# EasyEDA_SCH_5_5-OLED-to-RP5-MIPI.net
KiCad netlist of a schematic drawn in EasyEDA
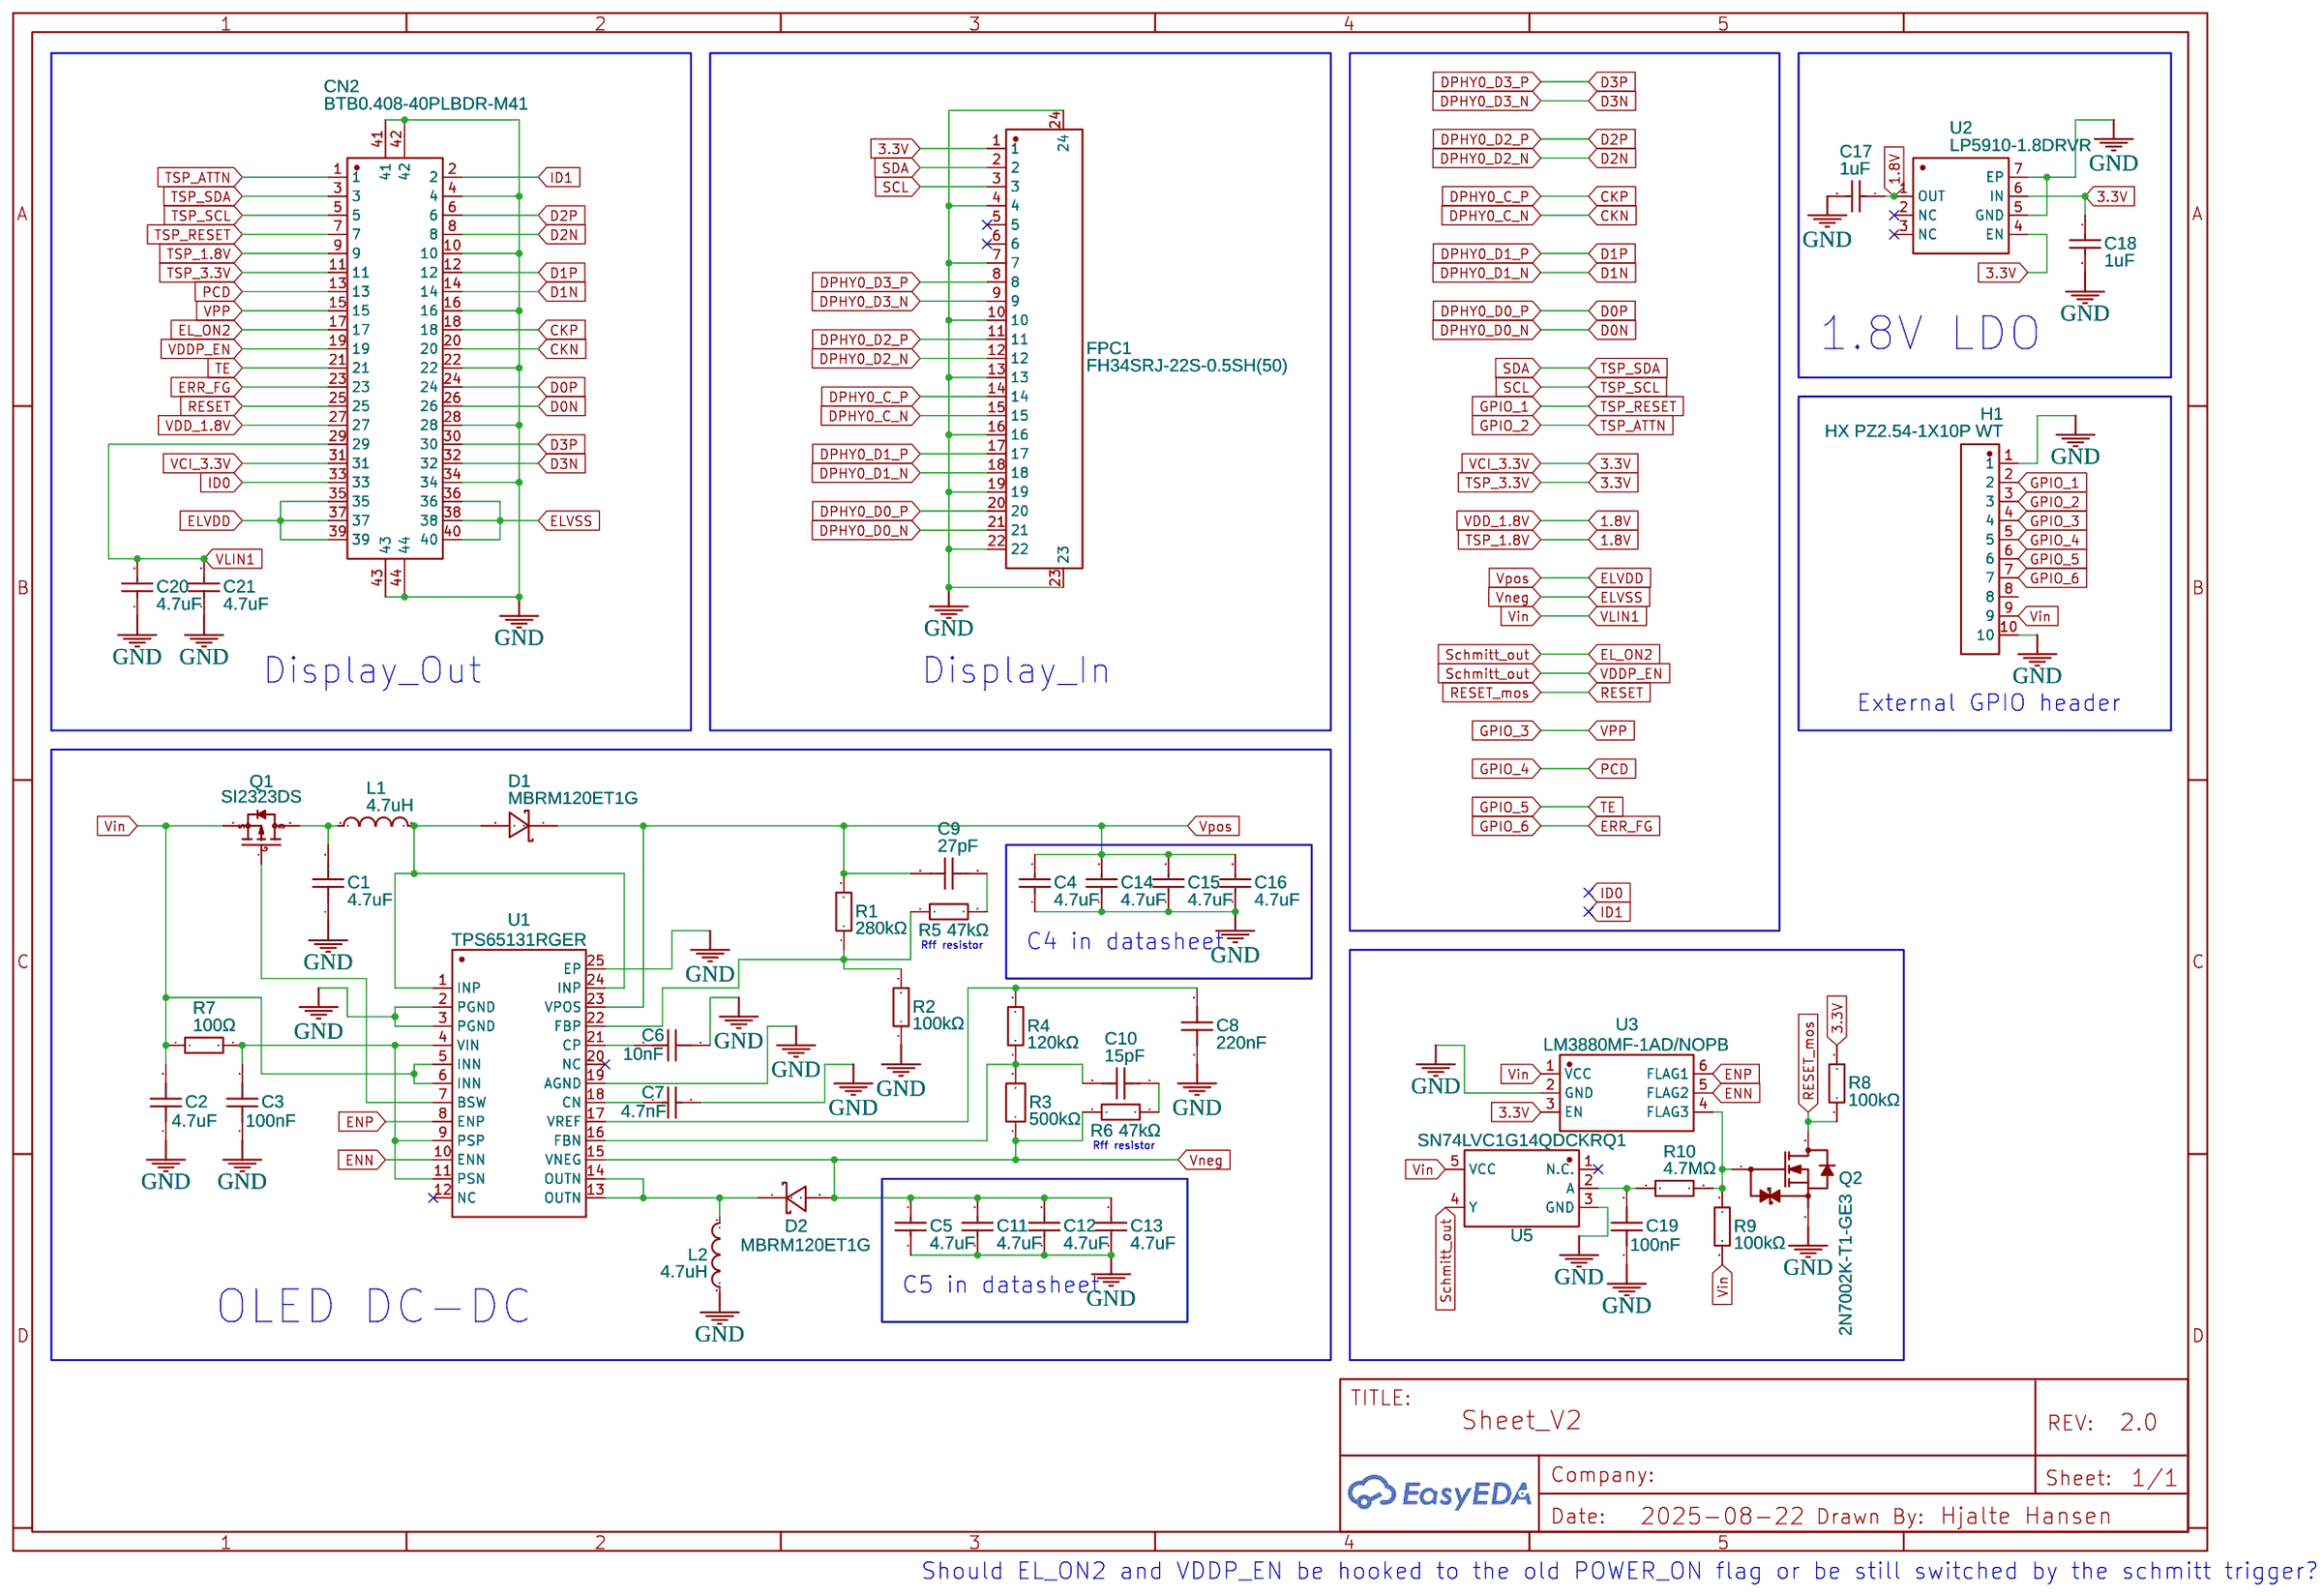
[diagram p0: schematic sheet]

(export (version "E")
  (design (tool "Eeschema 10.0.6"))
  (components
    (comp (ref "C1")
      (value "4.7uF")
      (fields
        (field (name "Manufacturer Part") "CL05A475MQ5NRNC")
        (field (name "Manufacturer") "SAMSUNG(三星)")
      )
      (libsource (lib "") (part "CL05A475MQ5NRNC_C307423"))
    )
    (comp (ref "C2")
      (value "4.7uF")
      (fields
        (field (name "Manufacturer Part") "CL05A475MQ5NRNC")
        (field (name "Manufacturer") "SAMSUNG(三星)")
      )
      (libsource (lib "") (part "CL05A475MQ5NRNC_C307423"))
    )
    (comp (ref "C3")
      (value "100nF")
      (fields
        (field (name "Manufacturer Part") "CL05B104KP5NNNC")
        (field (name "Manufacturer") "SAMSUNG(三星)")
      )
      (libsource (lib "") (part "CL05B104KP5NNNC"))
    )
    (comp (ref "C4")
      (value "4.7uF")
      (fields
        (field (name "Manufacturer Part") "CL21A475KAQNNNE")
        (field (name "Manufacturer") "SAMSUNG(三星)")
      )
      (libsource (lib "") (part "CL21A475KAQNNNE"))
    )
    (comp (ref "C5")
      (value "4.7uF")
      (fields
        (field (name "Manufacturer Part") "CL21A475KAQNNNE")
        (field (name "Manufacturer") "SAMSUNG(三星)")
      )
      (libsource (lib "") (part "CL21A475KAQNNNE"))
    )
    (comp (ref "C6")
      (value "10nF")
      (fields
        (field (name "Manufacturer Part") "CL05B103KO5NNNC")
        (field (name "Manufacturer") "SAMSUNG(三星)")
      )
      (libsource (lib "") (part "CL05B103KO5NNNC"))
    )
    (comp (ref "C7")
      (value "4.7nF")
      (fields
        (field (name "Manufacturer Part") "CL10B472KB8NNNC")
        (field (name "Manufacturer") "SAMSUNG(三星)")
      )
      (libsource (lib "") (part "CL10B472KB8NNNC"))
    )
    (comp (ref "C8")
      (value "220nF")
      (fields
        (field (name "Manufacturer Part") "CL05A224KQ5NNNC")
        (field (name "Manufacturer") "SAMSUNG(三星)")
      )
      (libsource (lib "") (part "CL05A224KQ5NNNC"))
    )
    (comp (ref "C9")
      (value "27pF")
      (fields
        (field (name "Manufacturer Part") "CC0603JRNPO7BN270")
        (field (name "Manufacturer") "YAGEO(国巨)")
      )
      (libsource (lib "") (part "CC0603JRNPO7BN270"))
    )
    (comp (ref "C10")
      (value "15pF")
      (fields
        (field (name "Manufacturer Part") "CC0402KRNPO7BN150")
        (field (name "Manufacturer") "YAGEO(国巨)")
      )
      (libsource (lib "") (part "CC0402KRNPO7BN150"))
    )
    (comp (ref "C11")
      (value "4.7uF")
      (fields
        (field (name "Manufacturer Part") "CL21A475KAQNNNE")
        (field (name "Manufacturer") "SAMSUNG(三星)")
      )
      (libsource (lib "") (part "CL21A475KAQNNNE"))
    )
    (comp (ref "C12")
      (value "4.7uF")
      (fields
        (field (name "Manufacturer Part") "CL21A475KAQNNNE")
        (field (name "Manufacturer") "SAMSUNG(三星)")
      )
      (libsource (lib "") (part "CL21A475KAQNNNE"))
    )
    (comp (ref "C13")
      (value "4.7uF")
      (fields
        (field (name "Manufacturer Part") "CL21A475KAQNNNE")
        (field (name "Manufacturer") "SAMSUNG(三星)")
      )
      (libsource (lib "") (part "CL21A475KAQNNNE"))
    )
    (comp (ref "C14")
      (value "4.7uF")
      (fields
        (field (name "Manufacturer Part") "CL21A475KAQNNNE")
        (field (name "Manufacturer") "SAMSUNG(三星)")
      )
      (libsource (lib "") (part "CL21A475KAQNNNE"))
    )
    (comp (ref "C15")
      (value "4.7uF")
      (fields
        (field (name "Manufacturer Part") "CL21A475KAQNNNE")
        (field (name "Manufacturer") "SAMSUNG(三星)")
      )
      (libsource (lib "") (part "CL21A475KAQNNNE"))
    )
    (comp (ref "C16")
      (value "4.7uF")
      (fields
        (field (name "Manufacturer Part") "CL21A475KAQNNNE")
        (field (name "Manufacturer") "SAMSUNG(三星)")
      )
      (libsource (lib "") (part "CL21A475KAQNNNE"))
    )
    (comp (ref "C17")
      (value "1uF")
      (fields
        (field (name "Manufacturer Part") "CL10A105KO8NNNC")
        (field (name "Manufacturer") "SAMSUNG(三星)")
      )
      (libsource (lib "") (part "CL10A105KO8NNNC_1"))
    )
    (comp (ref "C18")
      (value "1uF")
      (fields
        (field (name "Manufacturer Part") "CL10A105KO8NNNC")
        (field (name "Manufacturer") "SAMSUNG(三星)")
      )
      (libsource (lib "") (part "CL10A105KO8NNNC"))
    )
    (comp (ref "C19")
      (value "100nF")
      (fields
        (field (name "Manufacturer Part") "CL05B104KP5NNNC")
        (field (name "Manufacturer") "SAMSUNG(三星)")
      )
      (libsource (lib "") (part "CL05B104KP5NNNC"))
    )
    (comp (ref "C20")
      (value "4.7uF")
      (fields
        (field (name "Manufacturer Part") "CL21A475KAQNNNE")
        (field (name "Manufacturer") "SAMSUNG(三星)")
      )
      (libsource (lib "") (part "CL21A475KAQNNNE"))
    )
    (comp (ref "C21")
      (value "4.7uF")
      (fields
        (field (name "Manufacturer Part") "CL21A475KAQNNNE")
        (field (name "Manufacturer") "SAMSUNG(三星)")
      )
      (libsource (lib "") (part "CL21A475KAQNNNE"))
    )
    (comp (ref "CN2")
      (value "BTB0.408-40PLBDR-M41")
      (fields (field (name "Manufacturer") "XUNPU(讯普)"))
      (libsource (lib "") (part "BTB0.408-40PLBDR-M41"))
    )
    (comp (ref "D1")
      (value "MBRM120ET1G")
      (fields (field (name "Manufacturer") "onsemi(安森美)"))
      (libsource (lib "") (part "MBRM120ET1G"))
    )
    (comp (ref "D2")
      (value "MBRM120ET1G")
      (fields (field (name "Manufacturer") "onsemi(安森美)"))
      (libsource (lib "") (part "MBRM120ET1G_1"))
    )
    (comp (ref "FPC1")
      (value "FH34SRJ-22S-0.5SH(50)")
      (fields (field (name "Manufacturer") "HRS(广濑)"))
      (libsource (lib "") (part "FH34SRJ-22S-0.5SH(50)"))
    )
    (comp (ref "H1")
      (value "HX PZ2.54-1X10P WT")
      (fields
        (field (name "Manufacturer Part") "HX PZ2.54-1x10P WT")
        (field (name "Manufacturer") "hanxia(韩下)")
      )
      (libsource (lib "") (part "HX PZ2.54-1X10P WT"))
    )
    (comp (ref "L1")
      (value "4.7uH")
      (fields (field (name "Manufacturer Part") "FNR4020S4R7MT") (field (name "Manufacturer") "cjiang(长江微电)"))
      (libsource (lib "") (part "FNR4020S4R7MT"))
    )
    (comp (ref "L2")
      (value "4.7uH")
      (fields (field (name "Manufacturer Part") "FNR4020S4R7MT") (field (name "Manufacturer") "cjiang(长江微电)"))
      (libsource (lib "") (part "FNR4020S4R7MT_1"))
    )
    (comp (ref "Q1")
      (value "SI2323DS")
      (fields (field (name "Manufacturer") "TECH PUBLIC(台舟)"))
      (libsource (lib "") (part "SI2323DS"))
    )
    (comp (ref "Q2")
      (value "2N7002K-T1-GE3")
      (fields (field (name "Manufacturer") "VISHAY(威世)"))
      (libsource (lib "") (part "2N7002K-T1-GE3"))
    )
    (comp (ref "R1")
      (value "280kΩ")
      (fields
        (field (name "Manufacturer Part") "0603WAF2803T5E")
        (field (name "Manufacturer") "UNI-ROYAL(厚声)")
      )
      (libsource (lib "") (part "0603WAF2803T5E"))
    )
    (comp (ref "R2")
      (value "100kΩ")
      (fields
        (field (name "Manufacturer Part") "0603WAF1003T5E")
        (field (name "Manufacturer") "UNI-ROYAL(厚声)")
      )
      (libsource (lib "") (part "0603WAF1003T5E"))
    )
    (comp (ref "R3")
      (value "500kΩ")
      (fields (field (name "Manufacturer Part") "AR03BTCX5003N") (field (name "Manufacturer") "Viking(光颉)"))
      (libsource (lib "") (part "AR03BTCX5003N"))
    )
    (comp (ref "R4")
      (value "120kΩ")
      (fields
        (field (name "Manufacturer Part") "0603WAF1203T5E")
        (field (name "Manufacturer") "UNI-ROYAL(厚声)")
      )
      (libsource (lib "") (part "0603WAF1203T5E"))
    )
    (comp (ref "R5")
      (value "47kΩ")
      (fields (field (name "Manufacturer Part") "RC0603FR-0747KL") (field (name "Manufacturer") "YAGEO(国巨)"))
      (libsource (lib "") (part "RC0603FR-0747KL"))
    )
    (comp (ref "R6")
      (value "47kΩ")
      (fields (field (name "Manufacturer Part") "RC0603FR-0747KL") (field (name "Manufacturer") "YAGEO(国巨)"))
      (libsource (lib "") (part "RC0603FR-0747KL"))
    )
    (comp (ref "R7")
      (value "100Ω")
      (fields (field (name "Manufacturer Part") "RC0402FR-07100RL") (field (name "Manufacturer") "YAGEO(国巨)"))
      (libsource (lib "") (part "RC0402FR-07100RL"))
    )
    (comp (ref "R8")
      (value "100kΩ")
      (fields (field (name "Manufacturer Part") "RC0603FR-07100KL") (field (name "Manufacturer") "YAGEO(国巨)"))
      (libsource (lib "") (part "RC0603FR-07100KL"))
    )
    (comp (ref "R9")
      (value "100kΩ")
      (fields (field (name "Manufacturer Part") "RC0603FR-07100KL") (field (name "Manufacturer") "YAGEO(国巨)"))
      (libsource (lib "") (part "RC0603FR-07100KL"))
    )
    (comp (ref "R10")
      (value "4.7MΩ")
      (fields
        (field (name "Manufacturer Part") "0603WAF4704T5E")
        (field (name "Manufacturer") "UNI-ROYAL(厚声)")
      )
      (libsource (lib "") (part "0603WAF4704T5E"))
    )
    (comp (ref "U1")
      (value "TPS65131RGER")
      (fields (field (name "Manufacturer") "TI(德州仪器)"))
      (libsource (lib "") (part "TPS65131RGER"))
    )
    (comp (ref "U2")
      (value "LP5910-1.8DRVR")
      (fields (field (name "Manufacturer") "TI(德州仪器)"))
      (libsource (lib "") (part "LP5910-1.8DRVR"))
    )
    (comp (ref "U3")
      (value "LM3880MF-1AD/NOPB")
      (fields (field (name "Manufacturer") "TI(德州仪器)"))
      (libsource (lib "") (part "LM3880MF-1AD/NOPB"))
    )
    (comp (ref "U5")
      (value "SN74LVC1G14QDCKRQ1")
      (fields (field (name "Manufacturer") "TI(德州仪器)"))
      (libsource (lib "") (part "SN74LVC1G14QDCKRQ1"))
    )
  )
  (nets
    (net (code "1") (name "1.8V") (class "Default")
      (node (ref "C17") (pin "1") (pinfunction "1_1") (pintype "input"))
      (node (ref "CN2") (pin "27") (pinfunction "27_27") (pintype "unspecified"))
      (node (ref "CN2") (pin "9") (pinfunction "9_9") (pintype "unspecified"))
      (node (ref "U2") (pin "1") (pinfunction "OUT_1") (pintype "unspecified"))
    )
    (net (code "2") (name "3.3V") (class "Default")
      (node (ref "C18") (pin "1") (pinfunction "1_1") (pintype "input"))
      (node (ref "CN2") (pin "11") (pinfunction "11_11") (pintype "unspecified"))
      (node (ref "CN2") (pin "31") (pinfunction "31_31") (pintype "unspecified"))
      (node (ref "FPC1") (pin "1") (pinfunction "1_1") (pintype "unspecified"))
      (node (ref "R8") (pin "1") (pinfunction "1_1") (pintype "unspecified"))
      (node (ref "U2") (pin "4") (pinfunction "EN_4") (pintype "unspecified"))
      (node (ref "U2") (pin "6") (pinfunction "IN_6") (pintype "unspecified"))
      (node (ref "U3") (pin "3") (pinfunction "EN_3") (pintype "unspecified"))
    )
    (net (code "3") (name "CKN") (class "Default")
      (node (ref "CN2") (pin "20") (pinfunction "20_20") (pintype "unspecified"))
      (node (ref "FPC1") (pin "15") (pinfunction "15_15") (pintype "unspecified"))
    )
    (net (code "4") (name "CKP") (class "Default")
      (node (ref "CN2") (pin "18") (pinfunction "18_18") (pintype "unspecified"))
      (node (ref "FPC1") (pin "14") (pinfunction "14_14") (pintype "unspecified"))
    )
    (net (code "5") (name "D0N") (class "Default")
      (node (ref "CN2") (pin "26") (pinfunction "26_26") (pintype "unspecified"))
      (node (ref "FPC1") (pin "21") (pinfunction "21_21") (pintype "unspecified"))
    )
    (net (code "6") (name "D0P") (class "Default")
      (node (ref "CN2") (pin "24") (pinfunction "24_24") (pintype "unspecified"))
      (node (ref "FPC1") (pin "20") (pinfunction "20_20") (pintype "unspecified"))
    )
    (net (code "7") (name "D1N") (class "Default")
      (node (ref "CN2") (pin "14") (pinfunction "14_14") (pintype "unspecified"))
      (node (ref "FPC1") (pin "18") (pinfunction "18_18") (pintype "unspecified"))
    )
    (net (code "8") (name "D1P") (class "Default")
      (node (ref "CN2") (pin "12") (pinfunction "12_12") (pintype "unspecified"))
      (node (ref "FPC1") (pin "17") (pinfunction "17_17") (pintype "unspecified"))
    )
    (net (code "9") (name "D2N") (class "Default")
      (node (ref "CN2") (pin "8") (pinfunction "8_8") (pintype "unspecified"))
      (node (ref "FPC1") (pin "12") (pinfunction "12_12") (pintype "unspecified"))
    )
    (net (code "10") (name "D2P") (class "Default")
      (node (ref "CN2") (pin "6") (pinfunction "6_6") (pintype "unspecified"))
      (node (ref "FPC1") (pin "11") (pinfunction "11_11") (pintype "unspecified"))
    )
    (net (code "11") (name "D3N") (class "Default")
      (node (ref "CN2") (pin "32") (pinfunction "32_32") (pintype "unspecified"))
      (node (ref "FPC1") (pin "9") (pinfunction "9_9") (pintype "unspecified"))
    )
    (net (code "12") (name "D3P") (class "Default")
      (node (ref "CN2") (pin "30") (pinfunction "30_30") (pintype "unspecified"))
      (node (ref "FPC1") (pin "8") (pinfunction "8_8") (pintype "unspecified"))
    )
    (net (code "13") (name "ELVDD") (class "Default")
      (node (ref "C14") (pin "2") (pinfunction "2_2") (pintype "input"))
      (node (ref "C15") (pin "2") (pinfunction "2_2") (pintype "input"))
      (node (ref "C16") (pin "2") (pinfunction "2_2") (pintype "input"))
      (node (ref "C4") (pin "2") (pinfunction "2_2") (pintype "input"))
      (node (ref "C9") (pin "2") (pinfunction "2_2") (pintype "unspecified"))
      (node (ref "CN2") (pin "35") (pinfunction "35_35") (pintype "unspecified"))
      (node (ref "CN2") (pin "37") (pinfunction "37_37") (pintype "unspecified"))
      (node (ref "CN2") (pin "39") (pinfunction "39_39") (pintype "unspecified"))
      (node (ref "D1") (pin "1") (pinfunction "C_1") (pintype "unspecified"))
      (node (ref "R1") (pin "2") (pinfunction "2_2") (pintype "input"))
      (node (ref "U1") (pin "23") (pinfunction "VPOS_23") (pintype "unspecified"))
    )
    (net (code "14") (name "ELVSS") (class "Default")
      (node (ref "C11") (pin "2") (pinfunction "2_2") (pintype "input"))
      (node (ref "C12") (pin "2") (pinfunction "2_2") (pintype "input"))
      (node (ref "C13") (pin "2") (pinfunction "2_2") (pintype "input"))
      (node (ref "C5") (pin "2") (pinfunction "2_2") (pintype "input"))
      (node (ref "CN2") (pin "36") (pinfunction "36_36") (pintype "unspecified"))
      (node (ref "CN2") (pin "38") (pinfunction "38_38") (pintype "unspecified"))
      (node (ref "CN2") (pin "40") (pinfunction "40_40") (pintype "unspecified"))
      (node (ref "D2") (pin "2") (pinfunction "A_2") (pintype "unspecified"))
      (node (ref "R3") (pin "1") (pinfunction "1_1") (pintype "unspecified"))
      (node (ref "R6") (pin "1") (pinfunction "1_1") (pintype "input"))
      (node (ref "U1") (pin "15") (pinfunction "VNEG_15") (pintype "unspecified"))
    )
    (net (code "15") (name "EL_ON2") (class "Default")
      (node (ref "CN2") (pin "17") (pinfunction "17_17") (pintype "unspecified"))
      (node (ref "CN2") (pin "19") (pinfunction "19_19") (pintype "unspecified"))
      (node (ref "U5") (pin "4") (pinfunction "Y_4") (pintype "unspecified"))
    )
    (net (code "16") (name "ENN") (class "Default")
      (node (ref "U1") (pin "10") (pinfunction "ENN_10") (pintype "unspecified"))
      (node (ref "U3") (pin "5") (pinfunction "FLAG2_5") (pintype "unspecified"))
    )
    (net (code "17") (name "ENP") (class "Default")
      (node (ref "U1") (pin "8") (pinfunction "ENP_8") (pintype "unspecified"))
      (node (ref "U3") (pin "6") (pinfunction "FLAG1_6") (pintype "unspecified"))
    )
    (net (code "18") (name "ERR_FG") (class "Default")
      (node (ref "CN2") (pin "23") (pinfunction "23_23") (pintype "unspecified"))
      (node (ref "H1") (pin "7") (pinfunction "7_7") (pintype "unspecified"))
    )
    (net (code "19") (name "GND") (class "Default")
      (node (ref "C1") (pin "1") (pinfunction "1_1") (pintype "unspecified"))
      (node (ref "C11") (pin "1") (pinfunction "1_1") (pintype "input"))
      (node (ref "C12") (pin "1") (pinfunction "1_1") (pintype "input"))
      (node (ref "C13") (pin "1") (pinfunction "1_1") (pintype "input"))
      (node (ref "C14") (pin "1") (pinfunction "1_1") (pintype "input"))
      (node (ref "C15") (pin "1") (pinfunction "1_1") (pintype "input"))
      (node (ref "C16") (pin "1") (pinfunction "1_1") (pintype "input"))
      (node (ref "C17") (pin "2") (pinfunction "2_2") (pintype "input"))
      (node (ref "C18") (pin "2") (pinfunction "2_2") (pintype "input"))
      (node (ref "C19") (pin "1") (pinfunction "1_1") (pintype "unspecified"))
      (node (ref "C2") (pin "1") (pinfunction "1_1") (pintype "unspecified"))
      (node (ref "C20") (pin "1") (pinfunction "1_1") (pintype "input"))
      (node (ref "C21") (pin "1") (pinfunction "1_1") (pintype "input"))
      (node (ref "C3") (pin "1") (pinfunction "1_1") (pintype "unspecified"))
      (node (ref "C4") (pin "1") (pinfunction "1_1") (pintype "input"))
      (node (ref "C5") (pin "1") (pinfunction "1_1") (pintype "input"))
      (node (ref "C6") (pin "2") (pinfunction "2_2") (pintype "unspecified"))
      (node (ref "C7") (pin "2") (pinfunction "2_2") (pintype "input"))
      (node (ref "C8") (pin "1") (pinfunction "1_1") (pintype "unspecified"))
      (node (ref "CN2") (pin "10") (pinfunction "10_10") (pintype "unspecified"))
      (node (ref "CN2") (pin "16") (pinfunction "16_16") (pintype "unspecified"))
      (node (ref "CN2") (pin "22") (pinfunction "22_22") (pintype "unspecified"))
      (node (ref "CN2") (pin "28") (pinfunction "28_28") (pintype "unspecified"))
      (node (ref "CN2") (pin "34") (pinfunction "34_34") (pintype "unspecified"))
      (node (ref "CN2") (pin "4") (pinfunction "4_4") (pintype "unspecified"))
      (node (ref "CN2") (pin "41") (pinfunction "41_41") (pintype "unspecified"))
      (node (ref "CN2") (pin "42") (pinfunction "42_42") (pintype "unspecified"))
      (node (ref "CN2") (pin "43") (pinfunction "43_43") (pintype "unspecified"))
      (node (ref "CN2") (pin "44") (pinfunction "44_44") (pintype "unspecified"))
      (node (ref "FPC1") (pin "10") (pinfunction "10_10") (pintype "unspecified"))
      (node (ref "FPC1") (pin "13") (pinfunction "13_13") (pintype "unspecified"))
      (node (ref "FPC1") (pin "16") (pinfunction "16_16") (pintype "unspecified"))
      (node (ref "FPC1") (pin "19") (pinfunction "19_19") (pintype "unspecified"))
      (node (ref "FPC1") (pin "22") (pinfunction "22_22") (pintype "unspecified"))
      (node (ref "FPC1") (pin "23") (pinfunction "23_23") (pintype "unspecified"))
      (node (ref "FPC1") (pin "24") (pinfunction "24_24") (pintype "unspecified"))
      (node (ref "FPC1") (pin "4") (pinfunction "4_4") (pintype "unspecified"))
      (node (ref "FPC1") (pin "7") (pinfunction "7_7") (pintype "unspecified"))
      (node (ref "H1") (pin "1") (pinfunction "1_1") (pintype "unspecified"))
      (node (ref "H1") (pin "10") (pinfunction "10_10") (pintype "unspecified"))
      (node (ref "L2") (pin "2") (pinfunction "2_2") (pintype "unspecified"))
      (node (ref "Q2") (pin "2") (pinfunction "S_2") (pintype "unspecified"))
      (node (ref "R2") (pin "1") (pinfunction "1_1") (pintype "input"))
      (node (ref "U1") (pin "19") (pinfunction "AGND_19") (pintype "unspecified"))
      (node (ref "U1") (pin "2") (pinfunction "PGND_2") (pintype "unspecified"))
      (node (ref "U1") (pin "25") (pinfunction "EP_25") (pintype "unspecified"))
      (node (ref "U1") (pin "3") (pinfunction "PGND_3") (pintype "unspecified"))
      (node (ref "U2") (pin "5") (pinfunction "GND_5") (pintype "unspecified"))
      (node (ref "U2") (pin "7") (pinfunction "EP_7") (pintype "unspecified"))
      (node (ref "U3") (pin "2") (pinfunction "GND_2") (pintype "unspecified"))
      (node (ref "U5") (pin "3") (pinfunction "GND_3") (pintype "unspecified"))
    )
    (net (code "20") (name "GPIO_1") (class "Default")
      (node (ref "CN2") (pin "7") (pinfunction "7_7") (pintype "unspecified"))
      (node (ref "H1") (pin "2") (pinfunction "2_2") (pintype "unspecified"))
    )
    (net (code "21") (name "GPIO_2") (class "Default")
      (node (ref "CN2") (pin "1") (pinfunction "1_1") (pintype "unspecified"))
      (node (ref "H1") (pin "3") (pinfunction "3_3") (pintype "unspecified"))
    )
    (net (code "22") (name "GPIO_3") (class "Default")
      (node (ref "CN2") (pin "15") (pinfunction "15_15") (pintype "unspecified"))
      (node (ref "H1") (pin "4") (pinfunction "4_4") (pintype "unspecified"))
    )
    (net (code "23") (name "GPIO_4") (class "Default")
      (node (ref "CN2") (pin "13") (pinfunction "13_13") (pintype "unspecified"))
      (node (ref "H1") (pin "5") (pinfunction "5_5") (pintype "unspecified"))
    )
    (net (code "24") (name "GPIO_5") (class "Default")
      (node (ref "CN2") (pin "21") (pinfunction "21_21") (pintype "unspecified"))
      (node (ref "H1") (pin "6") (pinfunction "6_6") (pintype "unspecified"))
    )
    (net (code "25") (name "ID0") (class "Default")
      (node (ref "CN2") (pin "33") (pinfunction "33_33") (pintype "unspecified+no_connect"))
    )
    (net (code "26") (name "ID1") (class "Default")
      (node (ref "CN2") (pin "2") (pinfunction "2_2") (pintype "unspecified+no_connect"))
    )
    (net (code "27") (name "Net-(C9-Pad1)") (class "Default")
      (node (ref "C9") (pin "1") (pinfunction "1_1") (pintype "unspecified"))
      (node (ref "R5") (pin "2") (pinfunction "2_2") (pintype "input"))
    )
    (net (code "28") (name "Net-(C10-Pad1)") (class "Default")
      (node (ref "C10") (pin "1") (pinfunction "1_1") (pintype "unspecified"))
      (node (ref "R6") (pin "2") (pinfunction "2_2") (pintype "input"))
    )
    (net (code "29") (name "Net-(D1-A)") (class "Default")
      (node (ref "D1") (pin "2") (pinfunction "A_2") (pintype "unspecified"))
      (node (ref "L1") (pin "2") (pinfunction "2_2") (pintype "unspecified"))
      (node (ref "U1") (pin "1") (pinfunction "INP_1") (pintype "unspecified"))
      (node (ref "U1") (pin "24") (pinfunction "INP_24") (pintype "unspecified"))
    )
    (net (code "30") (name "Net-(D2-C)") (class "Default")
      (node (ref "D2") (pin "1") (pinfunction "C_1") (pintype "unspecified"))
      (node (ref "L2") (pin "1") (pinfunction "1_1") (pintype "unspecified"))
      (node (ref "U1") (pin "13") (pinfunction "OUTN_13") (pintype "unspecified"))
      (node (ref "U1") (pin "14") (pinfunction "OUTN_14") (pintype "unspecified"))
    )
    (net (code "31") (name "Net-(Q1-D)") (class "Default")
      (node (ref "C1") (pin "2") (pinfunction "2_2") (pintype "unspecified"))
      (node (ref "L1") (pin "1") (pinfunction "1_1") (pintype "unspecified"))
      (node (ref "Q1") (pin "3") (pinfunction "D_3") (pintype "unspecified"))
    )
    (net (code "32") (name "Net-(Q1-G)") (class "Default")
      (node (ref "Q1") (pin "1") (pinfunction "G_1") (pintype "unspecified"))
      (node (ref "U1") (pin "7") (pinfunction "BSW_7") (pintype "unspecified"))
    )
    (net (code "33") (name "Net-(Q2-G)") (class "Default")
      (node (ref "Q2") (pin "1") (pinfunction "G_1") (pintype "unspecified"))
      (node (ref "R10") (pin "2") (pinfunction "2_2") (pintype "input"))
      (node (ref "R9") (pin "1") (pinfunction "1_1") (pintype "unspecified"))
      (node (ref "U3") (pin "4") (pinfunction "FLAG3_4") (pintype "unspecified"))
    )
    (net (code "34") (name "Net-(U1-CN)") (class "Default")
      (node (ref "C7") (pin "1") (pinfunction "1_1") (pintype "input"))
      (node (ref "U1") (pin "18") (pinfunction "CN_18") (pintype "unspecified"))
    )
    (net (code "35") (name "Net-(U1-CP)") (class "Default")
      (node (ref "C6") (pin "1") (pinfunction "1_1") (pintype "unspecified"))
      (node (ref "U1") (pin "21") (pinfunction "CP_21") (pintype "unspecified"))
    )
    (net (code "36") (name "Net-(U1-FBN)") (class "Default")
      (node (ref "C10") (pin "2") (pinfunction "2_2") (pintype "unspecified"))
      (node (ref "R3") (pin "2") (pinfunction "2_2") (pintype "unspecified"))
      (node (ref "R4") (pin "1") (pinfunction "1_1") (pintype "input"))
      (node (ref "U1") (pin "16") (pinfunction "FBN_16") (pintype "unspecified"))
    )
    (net (code "37") (name "Net-(U1-FBP)") (class "Default")
      (node (ref "R1") (pin "1") (pinfunction "1_1") (pintype "input"))
      (node (ref "R2") (pin "2") (pinfunction "2_2") (pintype "input"))
      (node (ref "R5") (pin "1") (pinfunction "1_1") (pintype "input"))
      (node (ref "U1") (pin "22") (pinfunction "FBP_22") (pintype "unspecified"))
    )
    (net (code "38") (name "Net-(U1-PSN)") (class "Default")
      (node (ref "C3") (pin "2") (pinfunction "2_2") (pintype "unspecified"))
      (node (ref "R7") (pin "2") (pinfunction "2_2") (pintype "input"))
      (node (ref "U1") (pin "11") (pinfunction "PSN_11") (pintype "unspecified"))
      (node (ref "U1") (pin "4") (pinfunction "VIN_4") (pintype "unspecified"))
      (node (ref "U1") (pin "9") (pinfunction "PSP_9") (pintype "unspecified"))
    )
    (net (code "39") (name "Net-(U1-VREF)") (class "Default")
      (node (ref "C8") (pin "2") (pinfunction "2_2") (pintype "unspecified"))
      (node (ref "R4") (pin "2") (pinfunction "2_2") (pintype "input"))
      (node (ref "U1") (pin "17") (pinfunction "VREF_17") (pintype "unspecified"))
    )
    (net (code "40") (name "Net-(U5-A)") (class "Default")
      (node (ref "C19") (pin "2") (pinfunction "2_2") (pintype "unspecified"))
      (node (ref "R10") (pin "1") (pinfunction "1_1") (pintype "input"))
      (node (ref "U5") (pin "2") (pinfunction "A_2") (pintype "unspecified"))
    )
    (net (code "41") (name "RESET") (class "Default")
      (node (ref "CN2") (pin "25") (pinfunction "25_25") (pintype "unspecified"))
      (node (ref "Q2") (pin "3") (pinfunction "D_3") (pintype "unspecified"))
      (node (ref "R8") (pin "2") (pinfunction "2_2") (pintype "unspecified"))
    )
    (net (code "42") (name "SCL") (class "Default")
      (node (ref "CN2") (pin "5") (pinfunction "5_5") (pintype "unspecified"))
      (node (ref "FPC1") (pin "3") (pinfunction "3_3") (pintype "unspecified"))
    )
    (net (code "43") (name "SDA") (class "Default")
      (node (ref "CN2") (pin "3") (pinfunction "3_3") (pintype "unspecified"))
      (node (ref "FPC1") (pin "2") (pinfunction "2_2") (pintype "unspecified"))
    )
    (net (code "44") (name "VLIN1") (class "Default")
      (node (ref "C2") (pin "2") (pinfunction "2_2") (pintype "unspecified"))
      (node (ref "C20") (pin "2") (pinfunction "2_2") (pintype "input"))
      (node (ref "C21") (pin "2") (pinfunction "2_2") (pintype "input"))
      (node (ref "CN2") (pin "29") (pinfunction "29_29") (pintype "unspecified"))
      (node (ref "H1") (pin "9") (pinfunction "9_9") (pintype "unspecified"))
      (node (ref "Q1") (pin "2") (pinfunction "S_2") (pintype "unspecified"))
      (node (ref "R7") (pin "1") (pinfunction "1_1") (pintype "input"))
      (node (ref "R9") (pin "2") (pinfunction "2_2") (pintype "unspecified"))
      (node (ref "U1") (pin "5") (pinfunction "INN_5") (pintype "unspecified"))
      (node (ref "U1") (pin "6") (pinfunction "INN_6") (pintype "unspecified"))
      (node (ref "U3") (pin "1") (pinfunction "VCC_1") (pintype "unspecified"))
      (node (ref "U5") (pin "5") (pinfunction "VCC_5") (pintype "unspecified"))
    )
    (net (code "45") (name "unconnected-(FPC1-Pad5)") (class "Default")
      (node (ref "FPC1") (pin "5") (pinfunction "5_5") (pintype "unspecified+no_connect"))
    )
    (net (code "46") (name "unconnected-(FPC1-Pad6)") (class "Default")
      (node (ref "FPC1") (pin "6") (pinfunction "6_6") (pintype "unspecified+no_connect"))
    )
    (net (code "47") (name "unconnected-(H1-Pad8)") (class "Default")
      (node (ref "H1") (pin "8") (pinfunction "8_8") (pintype "unspecified"))
    )
    (net (code "48") (name "unconnected-(U1-NC-Pad12)") (class "Default")
      (node (ref "U1") (pin "12") (pinfunction "NC_12") (pintype "unspecified+no_connect"))
    )
    (net (code "49") (name "unconnected-(U1-NC-Pad20)") (class "Default")
      (node (ref "U1") (pin "20") (pinfunction "NC_20") (pintype "unspecified+no_connect"))
    )
    (net (code "50") (name "unconnected-(U2-NC-Pad2)") (class "Default")
      (node (ref "U2") (pin "2") (pinfunction "NC_2") (pintype "unspecified+no_connect"))
    )
    (net (code "51") (name "unconnected-(U2-NC-Pad3)") (class "Default")
      (node (ref "U2") (pin "3") (pinfunction "NC_3") (pintype "unspecified+no_connect"))
    )
    (net (code "52") (name "unconnected-(U5-N.C.-Pad1)") (class "Default")
      (node (ref "U5") (pin "1") (pinfunction "N.C._1") (pintype "unspecified+no_connect"))
    )
  )
)
